# RPi_Extension_weight.net
KiCad netlist of a schematic drawn in EAGLE
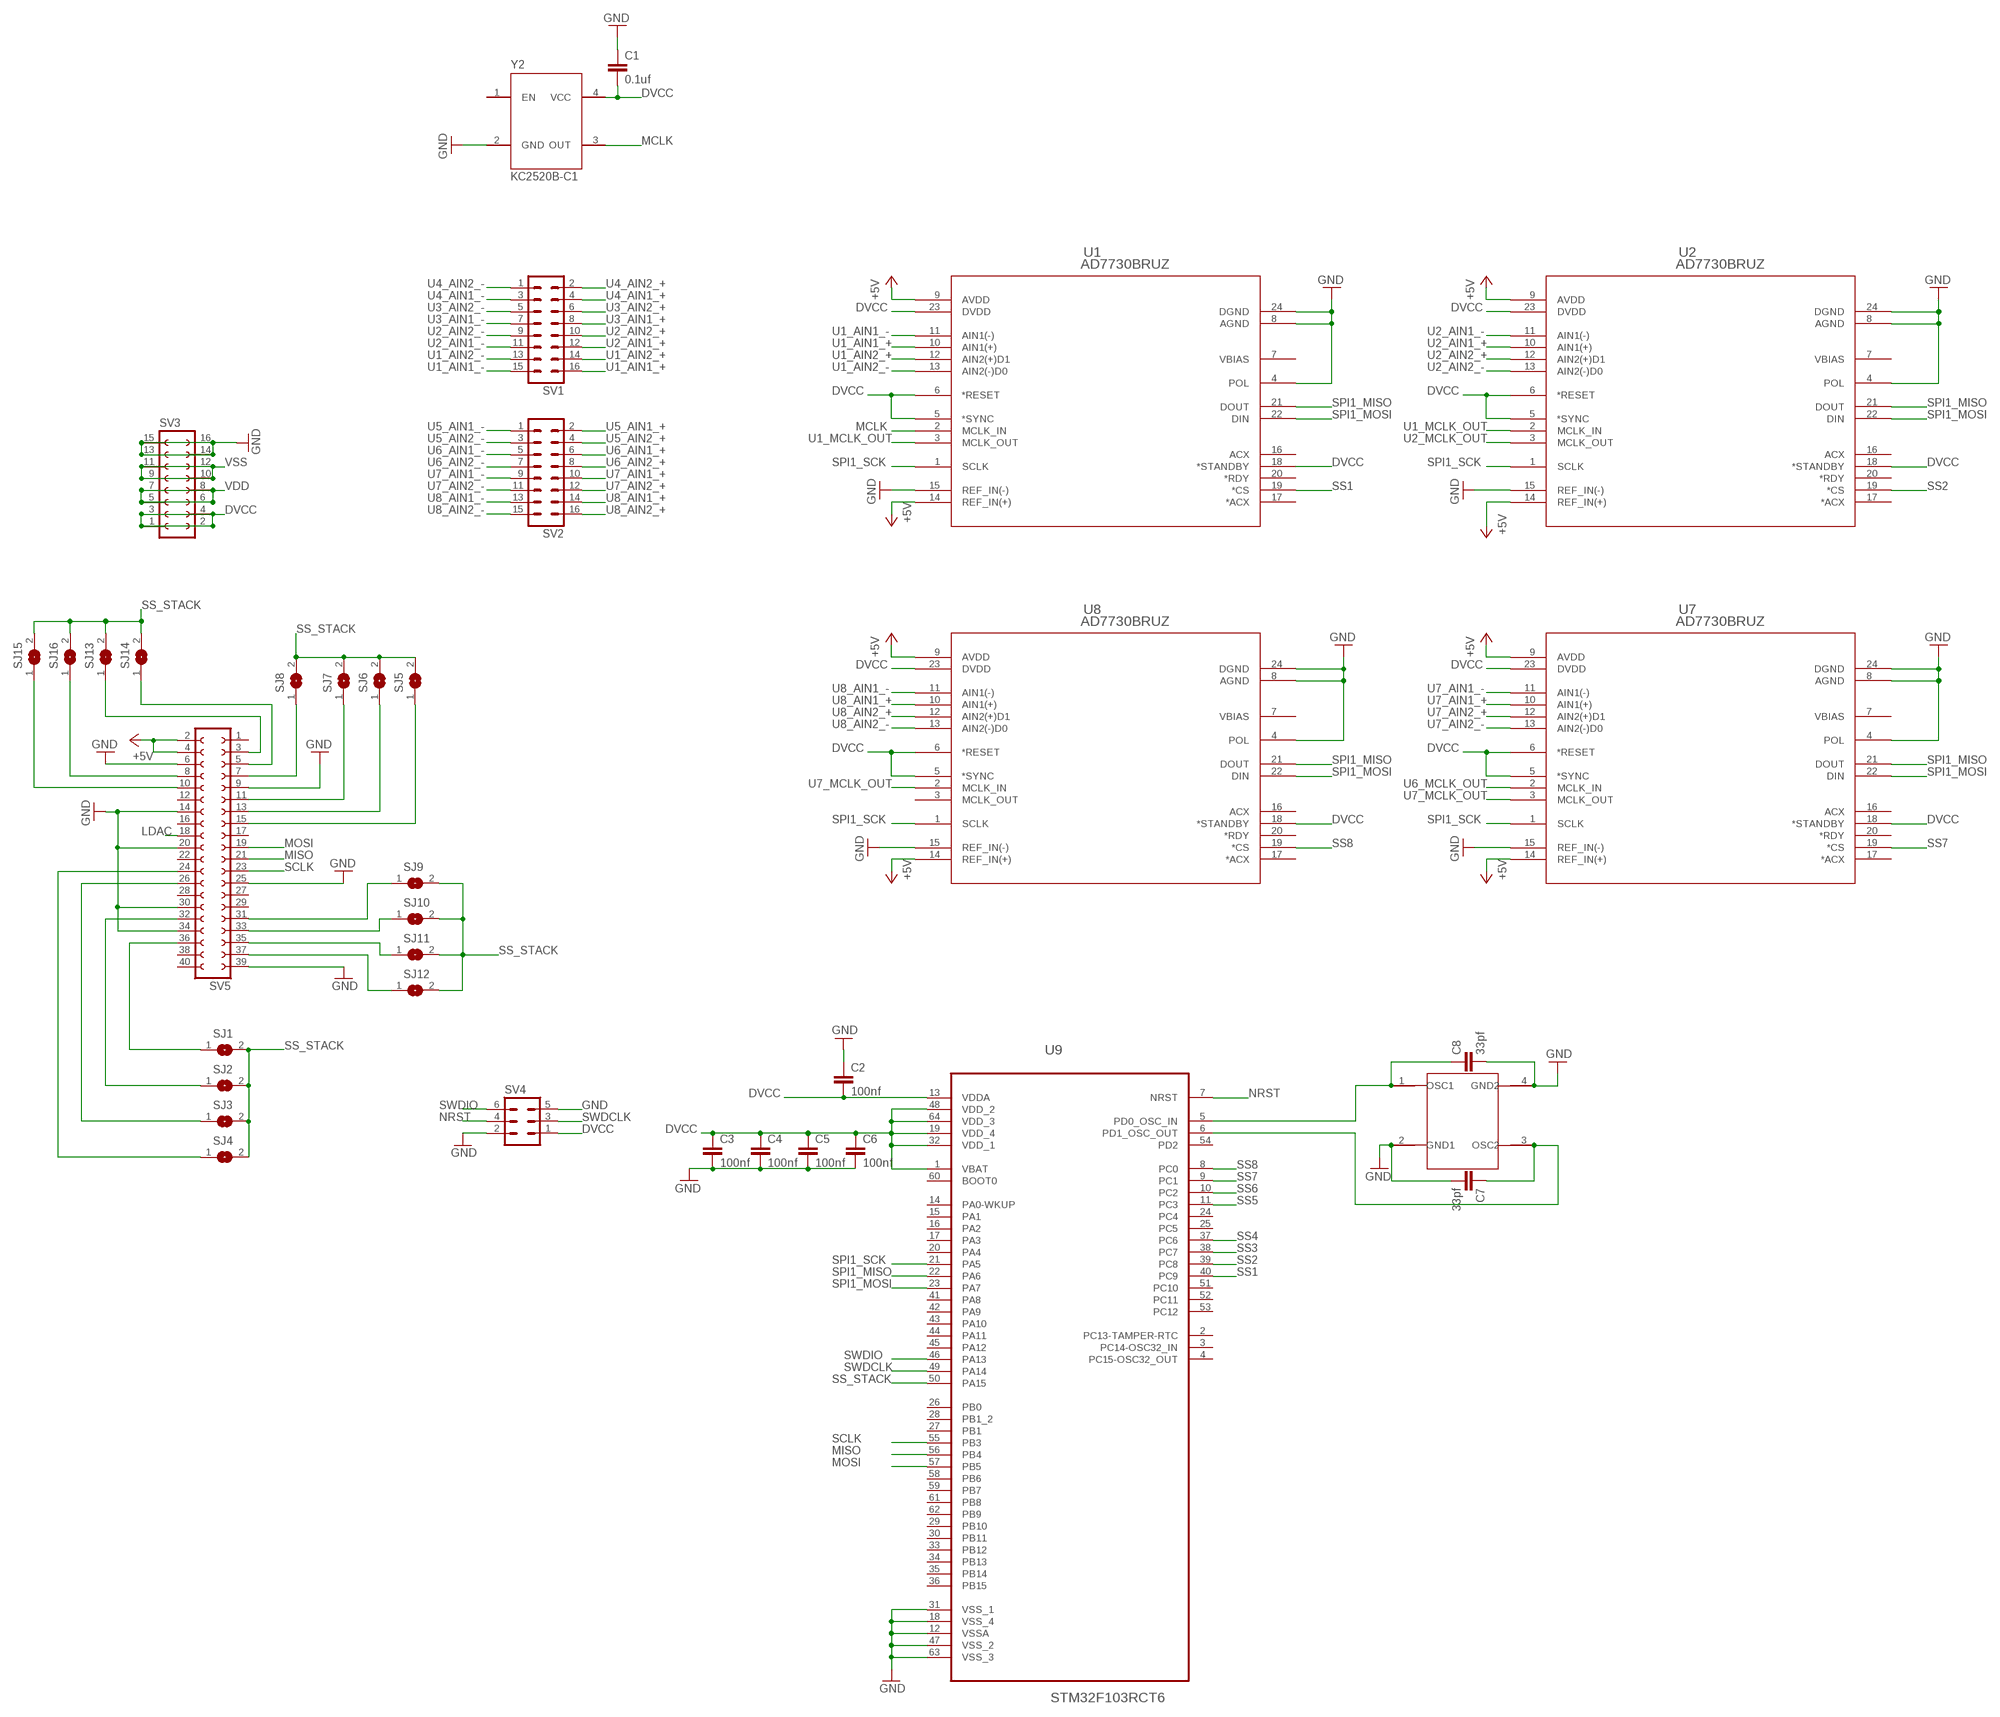
[diagram p0: schematic, sheet 1, part 1 of 2]
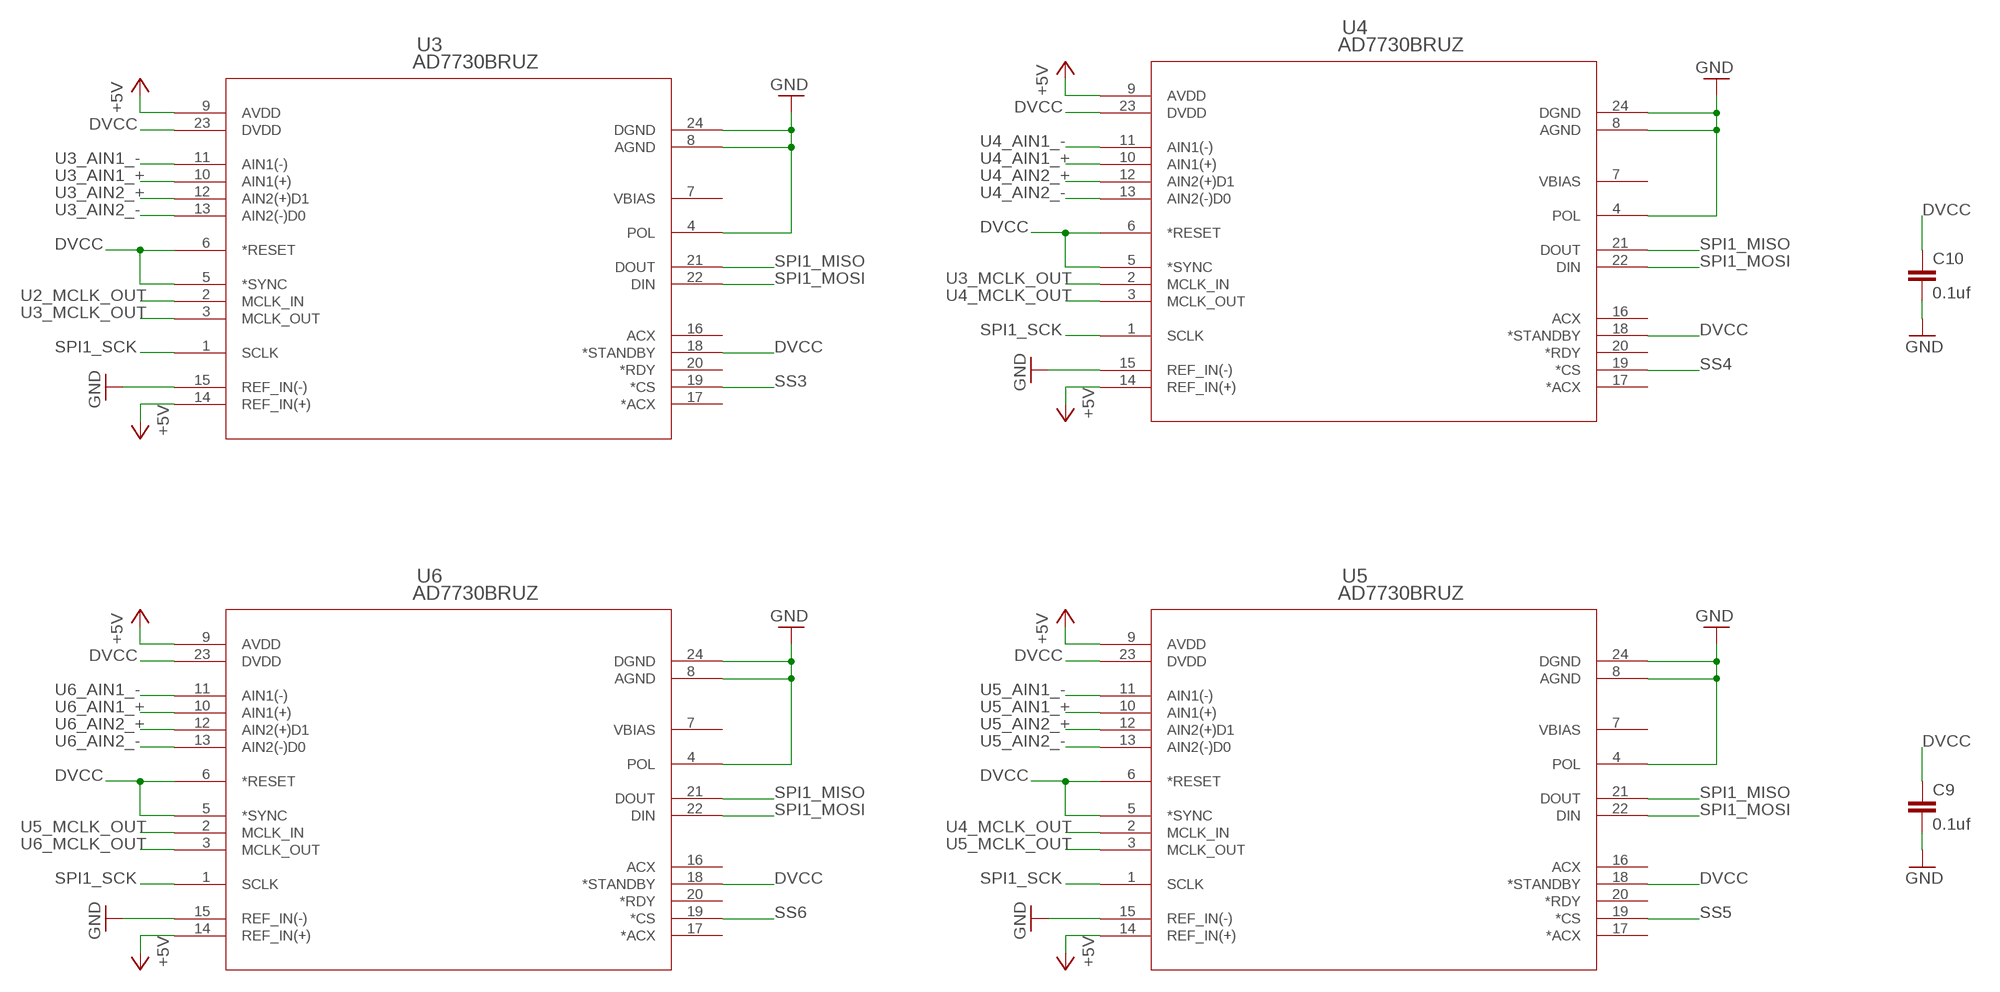
[diagram p1: schematic, sheet 1, part 2 of 2]

(export (version "E")
  (design (tool "Eeschema 10.0.6"))
  (components
    (comp (ref "C1")
      (value "0.1uf")
      (footprint "eagle-import:C0603")
      (libsource (lib "eagle-import") (part "C-EUC0603"))
    )
    (comp (ref "C2")
      (value "100nf")
      (footprint "eagle-import:C0603")
      (libsource (lib "eagle-import") (part "C-EUC0603"))
    )
    (comp (ref "C3")
      (value "100nf")
      (footprint "eagle-import:C0603")
      (libsource (lib "eagle-import") (part "C-EUC0603"))
    )
    (comp (ref "C4")
      (value "100nf")
      (footprint "eagle-import:C0603")
      (libsource (lib "eagle-import") (part "C-EUC0603"))
    )
    (comp (ref "C5")
      (value "100nf")
      (footprint "eagle-import:C0603")
      (libsource (lib "eagle-import") (part "C-EUC0603"))
    )
    (comp (ref "C6")
      (value "100nf")
      (footprint "eagle-import:C0603")
      (libsource (lib "eagle-import") (part "C-EUC0603"))
    )
    (comp (ref "C7")
      (value "33pf")
      (footprint "eagle-import:C0603")
      (libsource (lib "eagle-import") (part "C-EUC0603"))
    )
    (comp (ref "C8")
      (value "33pf")
      (footprint "eagle-import:C0603")
      (libsource (lib "eagle-import") (part "C-EUC0603"))
    )
    (comp (ref "C9")
      (value "0.1uf")
      (footprint "eagle-import:C0603")
      (libsource (lib "eagle-import") (part "C-EUC0603"))
    )
    (comp (ref "C10")
      (value "0.1uf")
      (footprint "eagle-import:C0603")
      (libsource (lib "eagle-import") (part "C-EUC0603"))
    )
    (comp (ref "SJ1") (value "SJ") (footprint "eagle-import:SJ") (libsource (lib "eagle-import") (part "SJ")))
    (comp (ref "SJ2") (value "SJ") (footprint "eagle-import:SJ") (libsource (lib "eagle-import") (part "SJ")))
    (comp (ref "SJ3") (value "SJ") (footprint "eagle-import:SJ") (libsource (lib "eagle-import") (part "SJ")))
    (comp (ref "SJ4") (value "SJ") (footprint "eagle-import:SJ") (libsource (lib "eagle-import") (part "SJ")))
    (comp (ref "SJ5") (value "SJ") (footprint "eagle-import:SJ") (libsource (lib "eagle-import") (part "SJ")))
    (comp (ref "SJ6") (value "SJ") (footprint "eagle-import:SJ") (libsource (lib "eagle-import") (part "SJ")))
    (comp (ref "SJ7") (value "SJ") (footprint "eagle-import:SJ") (libsource (lib "eagle-import") (part "SJ")))
    (comp (ref "SJ8") (value "SJ") (footprint "eagle-import:SJ") (libsource (lib "eagle-import") (part "SJ")))
    (comp (ref "SJ9") (value "SJ") (footprint "eagle-import:SJ") (libsource (lib "eagle-import") (part "SJ")))
    (comp (ref "SJ10")
      (value "SJ")
      (footprint "eagle-import:SJ")
      (libsource (lib "eagle-import") (part "SJ"))
    )
    (comp (ref "SJ11")
      (value "SJ")
      (footprint "eagle-import:SJ")
      (libsource (lib "eagle-import") (part "SJ"))
    )
    (comp (ref "SJ12")
      (value "SJ")
      (footprint "eagle-import:SJ")
      (libsource (lib "eagle-import") (part "SJ"))
    )
    (comp (ref "SJ13")
      (value "SJ")
      (footprint "eagle-import:SJ")
      (libsource (lib "eagle-import") (part "SJ"))
    )
    (comp (ref "SJ14")
      (value "SJ")
      (footprint "eagle-import:SJ")
      (libsource (lib "eagle-import") (part "SJ"))
    )
    (comp (ref "SJ15")
      (value "SJ")
      (footprint "eagle-import:SJ")
      (libsource (lib "eagle-import") (part "SJ"))
    )
    (comp (ref "SJ16")
      (value "SJ")
      (footprint "eagle-import:SJ")
      (libsource (lib "eagle-import") (part "SJ"))
    )
    (comp (ref "SV1")
      (value "MA08-2W")
      (footprint "eagle-import:MA08-2W")
      (libsource (lib "eagle-import") (part "MA08-2W"))
    )
    (comp (ref "SV2")
      (value "MA08-2W")
      (footprint "eagle-import:MA08-2W")
      (libsource (lib "eagle-import") (part "MA08-2W"))
    )
    (comp (ref "SV3")
      (value "FE08-2")
      (footprint "eagle-import:FE08-2")
      (libsource (lib "eagle-import") (part "FE08-2"))
    )
    (comp (ref "SV4")
      (value "MA03-2")
      (footprint "eagle-import:MA03-2")
      (libsource (lib "eagle-import") (part "MA03-2"))
    )
    (comp (ref "SV5")
      (value "FE20-2")
      (footprint "eagle-import:FE20-2")
      (libsource (lib "eagle-import") (part "FE20-2"))
    )
    (comp (ref "U1")
      (value "AD7730BRUZ")
      (footprint "eagle-import:RU_24")
      (libsource (lib "eagle-import") (part "AD7730BRUZ"))
    )
    (comp (ref "U2")
      (value "AD7730BRUZ")
      (footprint "eagle-import:RU_24")
      (libsource (lib "eagle-import") (part "AD7730BRUZ"))
    )
    (comp (ref "U3")
      (value "AD7730BRUZ")
      (footprint "eagle-import:RU_24")
      (libsource (lib "eagle-import") (part "AD7730BRUZ"))
    )
    (comp (ref "U4")
      (value "AD7730BRUZ")
      (footprint "eagle-import:RU_24")
      (libsource (lib "eagle-import") (part "AD7730BRUZ"))
    )
    (comp (ref "U5")
      (value "AD7730BRUZ")
      (footprint "eagle-import:RU_24")
      (libsource (lib "eagle-import") (part "AD7730BRUZ"))
    )
    (comp (ref "U6")
      (value "AD7730BRUZ")
      (footprint "eagle-import:RU_24")
      (libsource (lib "eagle-import") (part "AD7730BRUZ"))
    )
    (comp (ref "U7")
      (value "AD7730BRUZ")
      (footprint "eagle-import:RU_24")
      (libsource (lib "eagle-import") (part "AD7730BRUZ"))
    )
    (comp (ref "U8")
      (value "AD7730BRUZ")
      (footprint "eagle-import:RU_24")
      (libsource (lib "eagle-import") (part "AD7730BRUZ"))
    )
    (comp (ref "U9")
      (value "STM32F103RCT6")
      (footprint "eagle-import:QFP50P1200X1200X160-64N")
      (libsource (lib "eagle-import") (part "STM32F103RCT6"))
    )
    (comp (ref "Y1")
      (value "ABM3B")
      (footprint "eagle-import:ABM3B")
      (libsource (lib "eagle-import") (part "ABM3B"))
    )
    (comp (ref "Y2")
      (value "KC2520B-C1")
      (footprint "eagle-import:KC2520B-C1")
      (libsource (lib "eagle-import") (part "KC2520B-C1"))
    )
  )
  (nets
    (net (code "1") (name "+5V") (class "Default")
      (node (ref "SV5") (pin "2") (pinfunction "2_2") (pintype "passive"))
      (node (ref "SV5") (pin "4") (pinfunction "4_4") (pintype "passive"))
      (node (ref "U1") (pin "14") (pinfunction "REF_IN(+)_14") (pintype "passive"))
      (node (ref "U1") (pin "9") (pinfunction "AVDD_9") (pintype "passive"))
      (node (ref "U2") (pin "14") (pinfunction "REF_IN(+)_14") (pintype "passive"))
      (node (ref "U2") (pin "9") (pinfunction "AVDD_9") (pintype "passive"))
      (node (ref "U3") (pin "14") (pinfunction "REF_IN(+)_14") (pintype "passive"))
      (node (ref "U3") (pin "9") (pinfunction "AVDD_9") (pintype "passive"))
      (node (ref "U4") (pin "14") (pinfunction "REF_IN(+)_14") (pintype "passive"))
      (node (ref "U4") (pin "9") (pinfunction "AVDD_9") (pintype "passive"))
      (node (ref "U5") (pin "14") (pinfunction "REF_IN(+)_14") (pintype "passive"))
      (node (ref "U5") (pin "9") (pinfunction "AVDD_9") (pintype "passive"))
      (node (ref "U6") (pin "14") (pinfunction "REF_IN(+)_14") (pintype "passive"))
      (node (ref "U6") (pin "9") (pinfunction "AVDD_9") (pintype "passive"))
      (node (ref "U7") (pin "14") (pinfunction "REF_IN(+)_14") (pintype "passive"))
      (node (ref "U7") (pin "9") (pinfunction "AVDD_9") (pintype "passive"))
      (node (ref "U8") (pin "14") (pinfunction "REF_IN(+)_14") (pintype "passive"))
      (node (ref "U8") (pin "9") (pinfunction "AVDD_9") (pintype "passive"))
    )
    (net (code "2") (name "/DVCC") (class "Default")
      (node (ref "C1") (pin "2") (pinfunction "2_2") (pintype "passive"))
      (node (ref "C10") (pin "1") (pinfunction "1_1") (pintype "passive"))
      (node (ref "C2") (pin "2") (pinfunction "2_2") (pintype "passive"))
      (node (ref "C3") (pin "1") (pinfunction "1_1") (pintype "passive"))
      (node (ref "C4") (pin "1") (pinfunction "1_1") (pintype "passive"))
      (node (ref "C5") (pin "1") (pinfunction "1_1") (pintype "passive"))
      (node (ref "C6") (pin "1") (pinfunction "1_1") (pintype "passive"))
      (node (ref "C9") (pin "1") (pinfunction "1_1") (pintype "passive"))
      (node (ref "SV3") (pin "1") (pinfunction "1_1") (pintype "passive"))
      (node (ref "SV3") (pin "2") (pinfunction "2_2") (pintype "passive"))
      (node (ref "SV3") (pin "3") (pinfunction "3_3") (pintype "passive"))
      (node (ref "SV3") (pin "4") (pinfunction "4_4") (pintype "passive"))
      (node (ref "SV4") (pin "1") (pinfunction "1_1") (pintype "passive"))
      (node (ref "U1") (pin "18") (pinfunction "*STANDBY_18") (pintype "passive"))
      (node (ref "U1") (pin "23") (pinfunction "DVDD_23") (pintype "passive"))
      (node (ref "U1") (pin "5") (pinfunction "*SYNC_5") (pintype "passive"))
      (node (ref "U1") (pin "6") (pinfunction "*RESET_6") (pintype "passive"))
      (node (ref "U2") (pin "18") (pinfunction "*STANDBY_18") (pintype "passive"))
      (node (ref "U2") (pin "23") (pinfunction "DVDD_23") (pintype "passive"))
      (node (ref "U2") (pin "5") (pinfunction "*SYNC_5") (pintype "passive"))
      (node (ref "U2") (pin "6") (pinfunction "*RESET_6") (pintype "passive"))
      (node (ref "U3") (pin "18") (pinfunction "*STANDBY_18") (pintype "passive"))
      (node (ref "U3") (pin "23") (pinfunction "DVDD_23") (pintype "passive"))
      (node (ref "U3") (pin "5") (pinfunction "*SYNC_5") (pintype "passive"))
      (node (ref "U3") (pin "6") (pinfunction "*RESET_6") (pintype "passive"))
      (node (ref "U4") (pin "18") (pinfunction "*STANDBY_18") (pintype "passive"))
      (node (ref "U4") (pin "23") (pinfunction "DVDD_23") (pintype "passive"))
      (node (ref "U4") (pin "5") (pinfunction "*SYNC_5") (pintype "passive"))
      (node (ref "U4") (pin "6") (pinfunction "*RESET_6") (pintype "passive"))
      (node (ref "U5") (pin "18") (pinfunction "*STANDBY_18") (pintype "passive"))
      (node (ref "U5") (pin "23") (pinfunction "DVDD_23") (pintype "passive"))
      (node (ref "U5") (pin "5") (pinfunction "*SYNC_5") (pintype "passive"))
      (node (ref "U5") (pin "6") (pinfunction "*RESET_6") (pintype "passive"))
      (node (ref "U6") (pin "18") (pinfunction "*STANDBY_18") (pintype "passive"))
      (node (ref "U6") (pin "23") (pinfunction "DVDD_23") (pintype "passive"))
      (node (ref "U6") (pin "5") (pinfunction "*SYNC_5") (pintype "passive"))
      (node (ref "U6") (pin "6") (pinfunction "*RESET_6") (pintype "passive"))
      (node (ref "U7") (pin "18") (pinfunction "*STANDBY_18") (pintype "passive"))
      (node (ref "U7") (pin "23") (pinfunction "DVDD_23") (pintype "passive"))
      (node (ref "U7") (pin "5") (pinfunction "*SYNC_5") (pintype "passive"))
      (node (ref "U7") (pin "6") (pinfunction "*RESET_6") (pintype "passive"))
      (node (ref "U8") (pin "18") (pinfunction "*STANDBY_18") (pintype "passive"))
      (node (ref "U8") (pin "23") (pinfunction "DVDD_23") (pintype "passive"))
      (node (ref "U8") (pin "5") (pinfunction "*SYNC_5") (pintype "passive"))
      (node (ref "U8") (pin "6") (pinfunction "*RESET_6") (pintype "passive"))
      (node (ref "U9") (pin "1") (pinfunction "VBAT_1") (pintype "input"))
      (node (ref "U9") (pin "13") (pinfunction "VDDA_13") (pintype "power_in"))
      (node (ref "U9") (pin "19") (pinfunction "VDD_4_19") (pintype "power_in"))
      (node (ref "U9") (pin "32") (pinfunction "VDD_1_32") (pintype "power_in"))
      (node (ref "U9") (pin "48") (pinfunction "VDD_2_48") (pintype "power_in"))
      (node (ref "U9") (pin "64") (pinfunction "VDD_3_64") (pintype "power_in"))
      (node (ref "Y2") (pin "4") (pinfunction "VCC_4") (pintype "bidirectional"))
    )
    (net (code "3") (name "/LDAC") (class "Default")
      (node (ref "SV5") (pin "18") (pinfunction "18_18") (pintype "passive"))
    )
    (net (code "4") (name "/MCLK") (class "Default")
      (node (ref "U1") (pin "2") (pinfunction "MCLK_IN_2") (pintype "passive"))
      (node (ref "Y2") (pin "3") (pinfunction "OUT_3") (pintype "bidirectional"))
    )
    (net (code "5") (name "/MISO") (class "Default")
      (node (ref "SV5") (pin "21") (pinfunction "21_21") (pintype "passive"))
      (node (ref "U9") (pin "56") (pinfunction "PB4_56") (pintype "bidirectional"))
    )
    (net (code "6") (name "/MOSI") (class "Default")
      (node (ref "SV5") (pin "19") (pinfunction "19_19") (pintype "passive"))
      (node (ref "U9") (pin "57") (pinfunction "PB5_57") (pintype "bidirectional"))
    )
    (net (code "7") (name "/NRST") (class "Default")
      (node (ref "SV4") (pin "4") (pinfunction "4_4") (pintype "passive"))
      (node (ref "U9") (pin "7") (pinfunction "NRST_7") (pintype "output"))
    )
    (net (code "8") (name "/PB7") (class "Default")
      (node (ref "U9") (pin "59") (pinfunction "PB7_59") (pintype "power_in"))
    )
    (net (code "9") (name "/SCLK") (class "Default")
      (node (ref "SV5") (pin "23") (pinfunction "23_23") (pintype "passive"))
      (node (ref "U9") (pin "55") (pinfunction "PB3_55") (pintype "bidirectional"))
    )
    (net (code "10") (name "/SPI1_MISO") (class "Default")
      (node (ref "U1") (pin "21") (pinfunction "DOUT_21") (pintype "passive"))
      (node (ref "U2") (pin "21") (pinfunction "DOUT_21") (pintype "passive"))
      (node (ref "U3") (pin "21") (pinfunction "DOUT_21") (pintype "passive"))
      (node (ref "U4") (pin "21") (pinfunction "DOUT_21") (pintype "passive"))
      (node (ref "U5") (pin "21") (pinfunction "DOUT_21") (pintype "passive"))
      (node (ref "U6") (pin "21") (pinfunction "DOUT_21") (pintype "passive"))
      (node (ref "U7") (pin "21") (pinfunction "DOUT_21") (pintype "passive"))
      (node (ref "U8") (pin "21") (pinfunction "DOUT_21") (pintype "passive"))
      (node (ref "U9") (pin "22") (pinfunction "PA6_22") (pintype "bidirectional"))
    )
    (net (code "11") (name "/SPI1_MOSI") (class "Default")
      (node (ref "U1") (pin "22") (pinfunction "DIN_22") (pintype "passive"))
      (node (ref "U2") (pin "22") (pinfunction "DIN_22") (pintype "passive"))
      (node (ref "U3") (pin "22") (pinfunction "DIN_22") (pintype "passive"))
      (node (ref "U4") (pin "22") (pinfunction "DIN_22") (pintype "passive"))
      (node (ref "U5") (pin "22") (pinfunction "DIN_22") (pintype "passive"))
      (node (ref "U6") (pin "22") (pinfunction "DIN_22") (pintype "passive"))
      (node (ref "U7") (pin "22") (pinfunction "DIN_22") (pintype "passive"))
      (node (ref "U8") (pin "22") (pinfunction "DIN_22") (pintype "passive"))
      (node (ref "U9") (pin "23") (pinfunction "PA7_23") (pintype "power_in"))
    )
    (net (code "12") (name "/SPI1_SCK") (class "Default")
      (node (ref "U1") (pin "1") (pinfunction "SCLK_1") (pintype "passive"))
      (node (ref "U2") (pin "1") (pinfunction "SCLK_1") (pintype "passive"))
      (node (ref "U3") (pin "1") (pinfunction "SCLK_1") (pintype "passive"))
      (node (ref "U4") (pin "1") (pinfunction "SCLK_1") (pintype "passive"))
      (node (ref "U5") (pin "1") (pinfunction "SCLK_1") (pintype "passive"))
      (node (ref "U6") (pin "1") (pinfunction "SCLK_1") (pintype "passive"))
      (node (ref "U7") (pin "1") (pinfunction "SCLK_1") (pintype "passive"))
      (node (ref "U8") (pin "1") (pinfunction "SCLK_1") (pintype "passive"))
      (node (ref "U9") (pin "21") (pinfunction "PA5_21") (pintype "bidirectional"))
    )
    (net (code "13") (name "/SS1") (class "Default")
      (node (ref "U1") (pin "19") (pinfunction "*CS_19") (pintype "passive"))
      (node (ref "U9") (pin "40") (pinfunction "PC9_40") (pintype "bidirectional"))
    )
    (net (code "14") (name "/SS2") (class "Default")
      (node (ref "U2") (pin "19") (pinfunction "*CS_19") (pintype "passive"))
      (node (ref "U9") (pin "39") (pinfunction "PC8_39") (pintype "bidirectional"))
    )
    (net (code "15") (name "/SS3") (class "Default")
      (node (ref "U3") (pin "19") (pinfunction "*CS_19") (pintype "passive"))
      (node (ref "U9") (pin "38") (pinfunction "PC7_38") (pintype "bidirectional"))
    )
    (net (code "16") (name "/SS4") (class "Default")
      (node (ref "U4") (pin "19") (pinfunction "*CS_19") (pintype "passive"))
      (node (ref "U9") (pin "37") (pinfunction "PC6_37") (pintype "bidirectional"))
    )
    (net (code "17") (name "/SS5") (class "Default")
      (node (ref "U5") (pin "19") (pinfunction "*CS_19") (pintype "passive"))
      (node (ref "U9") (pin "11") (pinfunction "PC3_11") (pintype "bidirectional"))
    )
    (net (code "18") (name "/SS6") (class "Default")
      (node (ref "U6") (pin "19") (pinfunction "*CS_19") (pintype "passive"))
      (node (ref "U9") (pin "10") (pinfunction "PC2_10") (pintype "bidirectional"))
    )
    (net (code "19") (name "/SS7") (class "Default")
      (node (ref "U7") (pin "19") (pinfunction "*CS_19") (pintype "passive"))
      (node (ref "U9") (pin "9") (pinfunction "PC1_9") (pintype "bidirectional"))
    )
    (net (code "20") (name "/SS8") (class "Default")
      (node (ref "U8") (pin "19") (pinfunction "*CS_19") (pintype "passive"))
      (node (ref "U9") (pin "8") (pinfunction "PC0_8") (pintype "bidirectional"))
    )
    (net (code "21") (name "/SS_STACK") (class "Default")
      (node (ref "SJ1") (pin "2") (pinfunction "2_2") (pintype "passive"))
      (node (ref "SJ10") (pin "2") (pinfunction "2_2") (pintype "passive"))
      (node (ref "SJ11") (pin "2") (pinfunction "2_2") (pintype "passive"))
      (node (ref "SJ12") (pin "2") (pinfunction "2_2") (pintype "passive"))
      (node (ref "SJ13") (pin "2") (pinfunction "2_2") (pintype "passive"))
      (node (ref "SJ14") (pin "2") (pinfunction "2_2") (pintype "passive"))
      (node (ref "SJ15") (pin "2") (pinfunction "2_2") (pintype "passive"))
      (node (ref "SJ16") (pin "2") (pinfunction "2_2") (pintype "passive"))
      (node (ref "SJ2") (pin "2") (pinfunction "2_2") (pintype "passive"))
      (node (ref "SJ3") (pin "2") (pinfunction "2_2") (pintype "passive"))
      (node (ref "SJ4") (pin "2") (pinfunction "2_2") (pintype "passive"))
      (node (ref "SJ5") (pin "2") (pinfunction "2_2") (pintype "passive"))
      (node (ref "SJ6") (pin "2") (pinfunction "2_2") (pintype "passive"))
      (node (ref "SJ7") (pin "2") (pinfunction "2_2") (pintype "passive"))
      (node (ref "SJ8") (pin "2") (pinfunction "2_2") (pintype "passive"))
      (node (ref "SJ9") (pin "2") (pinfunction "2_2") (pintype "passive"))
      (node (ref "U9") (pin "50") (pinfunction "PA15_50") (pintype "bidirectional"))
    )
    (net (code "22") (name "/SWDCLK") (class "Default")
      (node (ref "SV4") (pin "3") (pinfunction "3_3") (pintype "passive"))
      (node (ref "U9") (pin "49") (pinfunction "PA14_49") (pintype "bidirectional"))
    )
    (net (code "23") (name "/SWDIO") (class "Default")
      (node (ref "SV4") (pin "6") (pinfunction "6_6") (pintype "passive"))
      (node (ref "U9") (pin "46") (pinfunction "PA13_46") (pintype "bidirectional"))
    )
    (net (code "24") (name "/U1_AIN1_+") (class "Default")
      (node (ref "SV1") (pin "16") (pinfunction "16_16") (pintype "passive"))
      (node (ref "U1") (pin "10") (pinfunction "AIN1(+)_10") (pintype "passive"))
    )
    (net (code "25") (name "/U1_AIN1_-") (class "Default")
      (node (ref "SV1") (pin "15") (pinfunction "15_15") (pintype "passive"))
      (node (ref "U1") (pin "11") (pinfunction "AIN1(-)_11") (pintype "passive"))
    )
    (net (code "26") (name "/U1_AIN2_+") (class "Default")
      (node (ref "SV1") (pin "14") (pinfunction "14_14") (pintype "passive"))
      (node (ref "U1") (pin "12") (pinfunction "AIN2(+)D1_12") (pintype "passive"))
    )
    (net (code "27") (name "/U1_AIN2_-") (class "Default")
      (node (ref "SV1") (pin "13") (pinfunction "13_13") (pintype "passive"))
      (node (ref "U1") (pin "13") (pinfunction "AIN2(-)D0_13") (pintype "passive"))
    )
    (net (code "28") (name "/U1_MCLK_OUT") (class "Default")
      (node (ref "U1") (pin "3") (pinfunction "MCLK_OUT_3") (pintype "passive"))
      (node (ref "U2") (pin "2") (pinfunction "MCLK_IN_2") (pintype "passive"))
    )
    (net (code "29") (name "/U2_AIN1_+") (class "Default")
      (node (ref "SV1") (pin "12") (pinfunction "12_12") (pintype "passive"))
      (node (ref "U2") (pin "10") (pinfunction "AIN1(+)_10") (pintype "passive"))
    )
    (net (code "30") (name "/U2_AIN1_-") (class "Default")
      (node (ref "SV1") (pin "11") (pinfunction "11_11") (pintype "passive"))
      (node (ref "U2") (pin "11") (pinfunction "AIN1(-)_11") (pintype "passive"))
    )
    (net (code "31") (name "/U2_AIN2_+") (class "Default")
      (node (ref "SV1") (pin "10") (pinfunction "10_10") (pintype "passive"))
      (node (ref "U2") (pin "12") (pinfunction "AIN2(+)D1_12") (pintype "passive"))
    )
    (net (code "32") (name "/U2_AIN2_-") (class "Default")
      (node (ref "SV1") (pin "9") (pinfunction "9_9") (pintype "passive"))
      (node (ref "U2") (pin "13") (pinfunction "AIN2(-)D0_13") (pintype "passive"))
    )
    (net (code "33") (name "/U2_MCLK_OUT") (class "Default")
      (node (ref "U2") (pin "3") (pinfunction "MCLK_OUT_3") (pintype "passive"))
      (node (ref "U3") (pin "2") (pinfunction "MCLK_IN_2") (pintype "passive"))
    )
    (net (code "34") (name "/U3_AIN1_+") (class "Default")
      (node (ref "SV1") (pin "8") (pinfunction "8_8") (pintype "passive"))
      (node (ref "U3") (pin "10") (pinfunction "AIN1(+)_10") (pintype "passive"))
    )
    (net (code "35") (name "/U3_AIN1_-") (class "Default")
      (node (ref "SV1") (pin "7") (pinfunction "7_7") (pintype "passive"))
      (node (ref "U3") (pin "11") (pinfunction "AIN1(-)_11") (pintype "passive"))
    )
    (net (code "36") (name "/U3_AIN2_+") (class "Default")
      (node (ref "SV1") (pin "6") (pinfunction "6_6") (pintype "passive"))
      (node (ref "U3") (pin "12") (pinfunction "AIN2(+)D1_12") (pintype "passive"))
    )
    (net (code "37") (name "/U3_AIN2_-") (class "Default")
      (node (ref "SV1") (pin "5") (pinfunction "5_5") (pintype "passive"))
      (node (ref "U3") (pin "13") (pinfunction "AIN2(-)D0_13") (pintype "passive"))
    )
    (net (code "38") (name "/U3_MCLK_OUT") (class "Default")
      (node (ref "U3") (pin "3") (pinfunction "MCLK_OUT_3") (pintype "passive"))
      (node (ref "U4") (pin "2") (pinfunction "MCLK_IN_2") (pintype "passive"))
    )
    (net (code "39") (name "/U4_AIN1_+") (class "Default")
      (node (ref "SV1") (pin "4") (pinfunction "4_4") (pintype "passive"))
      (node (ref "U4") (pin "10") (pinfunction "AIN1(+)_10") (pintype "passive"))
    )
    (net (code "40") (name "/U4_AIN1_-") (class "Default")
      (node (ref "SV1") (pin "3") (pinfunction "3_3") (pintype "passive"))
      (node (ref "U4") (pin "11") (pinfunction "AIN1(-)_11") (pintype "passive"))
    )
    (net (code "41") (name "/U4_AIN2_+") (class "Default")
      (node (ref "SV1") (pin "2") (pinfunction "2_2") (pintype "passive"))
      (node (ref "U4") (pin "12") (pinfunction "AIN2(+)D1_12") (pintype "passive"))
    )
    (net (code "42") (name "/U4_AIN2_-") (class "Default")
      (node (ref "SV1") (pin "1") (pinfunction "1_1") (pintype "passive"))
      (node (ref "U4") (pin "13") (pinfunction "AIN2(-)D0_13") (pintype "passive"))
    )
    (net (code "43") (name "/U4_MCLK_OUT") (class "Default")
      (node (ref "U4") (pin "3") (pinfunction "MCLK_OUT_3") (pintype "passive"))
      (node (ref "U5") (pin "2") (pinfunction "MCLK_IN_2") (pintype "passive"))
    )
    (net (code "44") (name "/U5_AIN1_+") (class "Default")
      (node (ref "SV2") (pin "2") (pinfunction "2_2") (pintype "passive"))
      (node (ref "U5") (pin "10") (pinfunction "AIN1(+)_10") (pintype "passive"))
    )
    (net (code "45") (name "/U5_AIN1_-") (class "Default")
      (node (ref "SV2") (pin "1") (pinfunction "1_1") (pintype "passive"))
      (node (ref "U5") (pin "11") (pinfunction "AIN1(-)_11") (pintype "passive"))
    )
    (net (code "46") (name "/U5_AIN2_+") (class "Default")
      (node (ref "SV2") (pin "4") (pinfunction "4_4") (pintype "passive"))
      (node (ref "U5") (pin "12") (pinfunction "AIN2(+)D1_12") (pintype "passive"))
    )
    (net (code "47") (name "/U5_AIN2_-") (class "Default")
      (node (ref "SV2") (pin "3") (pinfunction "3_3") (pintype "passive"))
      (node (ref "U5") (pin "13") (pinfunction "AIN2(-)D0_13") (pintype "passive"))
    )
    (net (code "48") (name "/U5_MCLK_OUT") (class "Default")
      (node (ref "U5") (pin "3") (pinfunction "MCLK_OUT_3") (pintype "passive"))
      (node (ref "U6") (pin "2") (pinfunction "MCLK_IN_2") (pintype "passive"))
    )
    (net (code "49") (name "/U6_AIN1_+") (class "Default")
      (node (ref "SV2") (pin "6") (pinfunction "6_6") (pintype "passive"))
      (node (ref "U6") (pin "10") (pinfunction "AIN1(+)_10") (pintype "passive"))
    )
    (net (code "50") (name "/U6_AIN1_-") (class "Default")
      (node (ref "SV2") (pin "5") (pinfunction "5_5") (pintype "passive"))
      (node (ref "U6") (pin "11") (pinfunction "AIN1(-)_11") (pintype "passive"))
    )
    (net (code "51") (name "/U6_AIN2_+") (class "Default")
      (node (ref "SV2") (pin "8") (pinfunction "8_8") (pintype "passive"))
      (node (ref "U6") (pin "12") (pinfunction "AIN2(+)D1_12") (pintype "passive"))
    )
    (net (code "52") (name "/U6_AIN2_-") (class "Default")
      (node (ref "SV2") (pin "7") (pinfunction "7_7") (pintype "passive"))
      (node (ref "U6") (pin "13") (pinfunction "AIN2(-)D0_13") (pintype "passive"))
    )
    (net (code "53") (name "/U6_MCLK_OUT") (class "Default")
      (node (ref "U6") (pin "3") (pinfunction "MCLK_OUT_3") (pintype "passive"))
      (node (ref "U7") (pin "2") (pinfunction "MCLK_IN_2") (pintype "passive"))
    )
    (net (code "54") (name "/U7_AIN1_+") (class "Default")
      (node (ref "SV2") (pin "10") (pinfunction "10_10") (pintype "passive"))
      (node (ref "U7") (pin "10") (pinfunction "AIN1(+)_10") (pintype "passive"))
    )
    (net (code "55") (name "/U7_AIN1_-") (class "Default")
      (node (ref "SV2") (pin "9") (pinfunction "9_9") (pintype "passive"))
      (node (ref "U7") (pin "11") (pinfunction "AIN1(-)_11") (pintype "passive"))
    )
    (net (code "56") (name "/U7_AIN2_+") (class "Default")
      (node (ref "SV2") (pin "12") (pinfunction "12_12") (pintype "passive"))
      (node (ref "U7") (pin "12") (pinfunction "AIN2(+)D1_12") (pintype "passive"))
    )
    (net (code "57") (name "/U7_AIN2_-") (class "Default")
      (node (ref "SV2") (pin "11") (pinfunction "11_11") (pintype "passive"))
      (node (ref "U7") (pin "13") (pinfunction "AIN2(-)D0_13") (pintype "passive"))
    )
    (net (code "58") (name "/U7_MCLK_OUT") (class "Default")
      (node (ref "U7") (pin "3") (pinfunction "MCLK_OUT_3") (pintype "passive"))
      (node (ref "U8") (pin "2") (pinfunction "MCLK_IN_2") (pintype "passive"))
    )
    (net (code "59") (name "/U8_AIN1_+") (class "Default")
      (node (ref "SV2") (pin "14") (pinfunction "14_14") (pintype "passive"))
      (node (ref "U8") (pin "10") (pinfunction "AIN1(+)_10") (pintype "passive"))
    )
    (net (code "60") (name "/U8_AIN1_-") (class "Default")
      (node (ref "SV2") (pin "13") (pinfunction "13_13") (pintype "passive"))
      (node (ref "U8") (pin "11") (pinfunction "AIN1(-)_11") (pintype "passive"))
    )
    (net (code "61") (name "/U8_AIN2_+") (class "Default")
      (node (ref "SV2") (pin "16") (pinfunction "16_16") (pintype "passive"))
      (node (ref "U8") (pin "12") (pinfunction "AIN2(+)D1_12") (pintype "passive"))
    )
    (net (code "62") (name "/U8_AIN2_-") (class "Default")
      (node (ref "SV2") (pin "15") (pinfunction "15_15") (pintype "passive"))
      (node (ref "U8") (pin "13") (pinfunction "AIN2(-)D0_13") (pintype "passive"))
    )
    (net (code "63") (name "/VDD") (class "Default")
      (node (ref "SV3") (pin "5") (pinfunction "5_5") (pintype "passive"))
      (node (ref "SV3") (pin "6") (pinfunction "6_6") (pintype "passive"))
      (node (ref "SV3") (pin "7") (pinfunction "7_7") (pintype "passive"))
      (node (ref "SV3") (pin "8") (pinfunction "8_8") (pintype "passive"))
    )
    (net (code "64") (name "/VSS") (class "Default")
      (node (ref "SV3") (pin "10") (pinfunction "10_10") (pintype "passive"))
      (node (ref "SV3") (pin "11") (pinfunction "11_11") (pintype "passive"))
      (node (ref "SV3") (pin "12") (pinfunction "12_12") (pintype "passive"))
      (node (ref "SV3") (pin "9") (pinfunction "9_9") (pintype "passive"))
    )
    (net (code "65") (name "GND") (class "Default")
      (node (ref "C1") (pin "1") (pinfunction "1_1") (pintype "passive"))
      (node (ref "C10") (pin "2") (pinfunction "2_2") (pintype "passive"))
      (node (ref "C2") (pin "1") (pinfunction "1_1") (pintype "passive"))
      (node (ref "C3") (pin "2") (pinfunction "2_2") (pintype "passive"))
      (node (ref "C4") (pin "2") (pinfunction "2_2") (pintype "passive"))
      (node (ref "C5") (pin "2") (pinfunction "2_2") (pintype "passive"))
      (node (ref "C6") (pin "2") (pinfunction "2_2") (pintype "passive"))
      (node (ref "C7") (pin "2") (pinfunction "2_2") (pintype "passive"))
      (node (ref "C8") (pin "2") (pinfunction "2_2") (pintype "passive"))
      (node (ref "C9") (pin "2") (pinfunction "2_2") (pintype "passive"))
      (node (ref "SV3") (pin "13") (pinfunction "13_13") (pintype "passive"))
      (node (ref "SV3") (pin "14") (pinfunction "14_14") (pintype "passive"))
      (node (ref "SV3") (pin "15") (pinfunction "15_15") (pintype "passive"))
      (node (ref "SV3") (pin "16") (pinfunction "16_16") (pintype "passive"))
      (node (ref "SV4") (pin "2") (pinfunction "2_2") (pintype "passive"))
      (node (ref "SV4") (pin "5") (pinfunction "5_5") (pintype "passive"))
      (node (ref "SV5") (pin "14") (pinfunction "14_14") (pintype "passive"))
      (node (ref "SV5") (pin "20") (pinfunction "20_20") (pintype "passive"))
      (node (ref "SV5") (pin "25") (pinfunction "25_25") (pintype "passive"))
      (node (ref "SV5") (pin "30") (pinfunction "30_30") (pintype "passive"))
      (node (ref "SV5") (pin "34") (pinfunction "34_34") (pintype "passive"))
      (node (ref "SV5") (pin "39") (pinfunction "39_39") (pintype "passive"))
      (node (ref "SV5") (pin "6") (pinfunction "6_6") (pintype "passive"))
      (node (ref "SV5") (pin "9") (pinfunction "9_9") (pintype "passive"))
      (node (ref "U1") (pin "15") (pinfunction "REF_IN(-)_15") (pintype "passive"))
      (node (ref "U1") (pin "24") (pinfunction "DGND_24") (pintype "passive"))
      (node (ref "U1") (pin "4") (pinfunction "POL_4") (pintype "passive"))
      (node (ref "U1") (pin "8") (pinfunction "AGND_8") (pintype "passive"))
      (node (ref "U2") (pin "15") (pinfunction "REF_IN(-)_15") (pintype "passive"))
      (node (ref "U2") (pin "24") (pinfunction "DGND_24") (pintype "passive"))
      (node (ref "U2") (pin "4") (pinfunction "POL_4") (pintype "passive"))
      (node (ref "U2") (pin "8") (pinfunction "AGND_8") (pintype "passive"))
      (node (ref "U3") (pin "15") (pinfunction "REF_IN(-)_15") (pintype "passive"))
      (node (ref "U3") (pin "24") (pinfunction "DGND_24") (pintype "passive"))
      (node (ref "U3") (pin "4") (pinfunction "POL_4") (pintype "passive"))
      (node (ref "U3") (pin "8") (pinfunction "AGND_8") (pintype "passive"))
      (node (ref "U4") (pin "15") (pinfunction "REF_IN(-)_15") (pintype "passive"))
      (node (ref "U4") (pin "24") (pinfunction "DGND_24") (pintype "passive"))
      (node (ref "U4") (pin "4") (pinfunction "POL_4") (pintype "passive"))
      (node (ref "U4") (pin "8") (pinfunction "AGND_8") (pintype "passive"))
      (node (ref "U5") (pin "15") (pinfunction "REF_IN(-)_15") (pintype "passive"))
      (node (ref "U5") (pin "24") (pinfunction "DGND_24") (pintype "passive"))
      (node (ref "U5") (pin "4") (pinfunction "POL_4") (pintype "passive"))
      (node (ref "U5") (pin "8") (pinfunction "AGND_8") (pintype "passive"))
      (node (ref "U6") (pin "15") (pinfunction "REF_IN(-)_15") (pintype "passive"))
      (node (ref "U6") (pin "24") (pinfunction "DGND_24") (pintype "passive"))
      (node (ref "U6") (pin "4") (pinfunction "POL_4") (pintype "passive"))
      (node (ref "U6") (pin "8") (pinfunction "AGND_8") (pintype "passive"))
      (node (ref "U7") (pin "15") (pinfunction "REF_IN(-)_15") (pintype "passive"))
      (node (ref "U7") (pin "24") (pinfunction "DGND_24") (pintype "passive"))
      (node (ref "U7") (pin "4") (pinfunction "POL_4") (pintype "passive"))
      (node (ref "U7") (pin "8") (pinfunction "AGND_8") (pintype "passive"))
      (node (ref "U8") (pin "15") (pinfunction "REF_IN(-)_15") (pintype "passive"))
      (node (ref "U8") (pin "24") (pinfunction "DGND_24") (pintype "passive"))
      (node (ref "U8") (pin "4") (pinfunction "POL_4") (pintype "passive"))
      (node (ref "U8") (pin "8") (pinfunction "AGND_8") (pintype "passive"))
      (node (ref "U9") (pin "12") (pinfunction "VSSA_12") (pintype "passive"))
      (node (ref "U9") (pin "18") (pinfunction "VSS_4_18") (pintype "passive"))
      (node (ref "U9") (pin "31") (pinfunction "VSS_1_31") (pintype "passive"))
      (node (ref "U9") (pin "47") (pinfunction "VSS_2_47") (pintype "passive"))
      (node (ref "U9") (pin "63") (pinfunction "VSS_3_63") (pintype "passive"))
      (node (ref "Y1") (pin "2") (pinfunction "GND1_2") (pintype "bidirectional"))
      (node (ref "Y1") (pin "4") (pinfunction "GND2_4") (pintype "bidirectional"))
      (node (ref "Y2") (pin "2") (pinfunction "GND_2") (pintype "bidirectional"))
    )
    (net (code "66") (name "Net-(SJ1-Pad1)") (class "Default")
      (node (ref "SJ1") (pin "1") (pinfunction "1_1") (pintype "passive"))
      (node (ref "SV5") (pin "36") (pinfunction "36_36") (pintype "passive"))
    )
    (net (code "67") (name "Net-(SJ2-Pad1)") (class "Default")
      (node (ref "SJ2") (pin "1") (pinfunction "1_1") (pintype "passive"))
      (node (ref "SV5") (pin "32") (pinfunction "32_32") (pintype "passive"))
    )
    (net (code "68") (name "Net-(SJ3-Pad1)") (class "Default")
      (node (ref "SJ3") (pin "1") (pinfunction "1_1") (pintype "passive"))
      (node (ref "SV5") (pin "26") (pinfunction "26_26") (pintype "passive"))
    )
    (net (code "69") (name "Net-(SJ4-Pad1)") (class "Default")
      (node (ref "SJ4") (pin "1") (pinfunction "1_1") (pintype "passive"))
      (node (ref "SV5") (pin "24") (pinfunction "24_24") (pintype "passive"))
    )
    (net (code "70") (name "Net-(SJ5-Pad1)") (class "Default")
      (node (ref "SJ5") (pin "1") (pinfunction "1_1") (pintype "passive"))
      (node (ref "SV5") (pin "15") (pinfunction "15_15") (pintype "passive"))
    )
    (net (code "71") (name "Net-(SJ6-Pad1)") (class "Default")
      (node (ref "SJ6") (pin "1") (pinfunction "1_1") (pintype "passive"))
      (node (ref "SV5") (pin "13") (pinfunction "13_13") (pintype "passive"))
    )
    (net (code "72") (name "Net-(SJ7-Pad1)") (class "Default")
      (node (ref "SJ7") (pin "1") (pinfunction "1_1") (pintype "passive"))
      (node (ref "SV5") (pin "11") (pinfunction "11_11") (pintype "passive"))
    )
    (net (code "73") (name "Net-(SJ8-Pad1)") (class "Default")
      (node (ref "SJ8") (pin "1") (pinfunction "1_1") (pintype "passive"))
      (node (ref "SV5") (pin "7") (pinfunction "7_7") (pintype "passive"))
    )
    (net (code "74") (name "Net-(SJ9-Pad1)") (class "Default")
      (node (ref "SJ9") (pin "1") (pinfunction "1_1") (pintype "passive"))
      (node (ref "SV5") (pin "31") (pinfunction "31_31") (pintype "passive"))
    )
    (net (code "75") (name "Net-(SJ10-Pad1)") (class "Default")
      (node (ref "SJ10") (pin "1") (pinfunction "1_1") (pintype "passive"))
      (node (ref "SV5") (pin "33") (pinfunction "33_33") (pintype "passive"))
    )
    (net (code "76") (name "Net-(SJ11-Pad1)") (class "Default")
      (node (ref "SJ11") (pin "1") (pinfunction "1_1") (pintype "passive"))
      (node (ref "SV5") (pin "35") (pinfunction "35_35") (pintype "passive"))
    )
    (net (code "77") (name "Net-(SJ12-Pad1)") (class "Default")
      (node (ref "SJ12") (pin "1") (pinfunction "1_1") (pintype "passive"))
      (node (ref "SV5") (pin "37") (pinfunction "37_37") (pintype "passive"))
    )
    (net (code "78") (name "Net-(SJ13-Pad1)") (class "Default")
      (node (ref "SJ13") (pin "1") (pinfunction "1_1") (pintype "passive"))
      (node (ref "SV5") (pin "3") (pinfunction "3_3") (pintype "passive"))
    )
    (net (code "79") (name "Net-(SJ14-Pad1)") (class "Default")
      (node (ref "SJ14") (pin "1") (pinfunction "1_1") (pintype "passive"))
      (node (ref "SV5") (pin "5") (pinfunction "5_5") (pintype "passive"))
    )
    (net (code "80") (name "Net-(SJ15-Pad1)") (class "Default")
      (node (ref "SJ15") (pin "1") (pinfunction "1_1") (pintype "passive"))
      (node (ref "SV5") (pin "10") (pinfunction "10_10") (pintype "passive"))
    )
    (net (code "81") (name "Net-(SJ16-Pad1)") (class "Default")
      (node (ref "SJ16") (pin "1") (pinfunction "1_1") (pintype "passive"))
      (node (ref "SV5") (pin "8") (pinfunction "8_8") (pintype "passive"))
    )
    (net (code "82") (name "Net-(U9-PD0_OSC_IN)") (class "Default")
      (node (ref "C8") (pin "1") (pinfunction "1_1") (pintype "passive"))
      (node (ref "U9") (pin "5") (pinfunction "PD0_OSC_IN_5") (pintype "input"))
      (node (ref "Y1") (pin "1") (pinfunction "OSC1_1") (pintype "bidirectional"))
    )
    (net (code "83") (name "Net-(U9-PD1_OSC_OUT)") (class "Default")
      (node (ref "C7") (pin "1") (pinfunction "1_1") (pintype "passive"))
      (node (ref "U9") (pin "6") (pinfunction "PD1_OSC_OUT_6") (pintype "output"))
      (node (ref "Y1") (pin "3") (pinfunction "OSC2_3") (pintype "bidirectional"))
    )
    (net (code "84") (name "unconnected-(SV5-Pad1)") (class "Default")
      (node (ref "SV5") (pin "1") (pinfunction "1_1") (pintype "passive"))
    )
    (net (code "85") (name "unconnected-(SV5-Pad12)") (class "Default")
      (node (ref "SV5") (pin "12") (pinfunction "12_12") (pintype "passive"))
    )
    (net (code "86") (name "unconnected-(SV5-Pad16)") (class "Default")
      (node (ref "SV5") (pin "16") (pinfunction "16_16") (pintype "passive"))
    )
    (net (code "87") (name "unconnected-(SV5-Pad17)") (class "Default")
      (node (ref "SV5") (pin "17") (pinfunction "17_17") (pintype "passive"))
    )
    (net (code "88") (name "unconnected-(SV5-Pad22)") (class "Default")
      (node (ref "SV5") (pin "22") (pinfunction "22_22") (pintype "passive"))
    )
    (net (code "89") (name "unconnected-(SV5-Pad27)") (class "Default")
      (node (ref "SV5") (pin "27") (pinfunction "27_27") (pintype "passive"))
    )
    (net (code "90") (name "unconnected-(SV5-Pad28)") (class "Default")
      (node (ref "SV5") (pin "28") (pinfunction "28_28") (pintype "passive"))
    )
    (net (code "91") (name "unconnected-(SV5-Pad29)") (class "Default")
      (node (ref "SV5") (pin "29") (pinfunction "29_29") (pintype "passive"))
    )
    (net (code "92") (name "unconnected-(SV5-Pad38)") (class "Default")
      (node (ref "SV5") (pin "38") (pinfunction "38_38") (pintype "passive"))
    )
    (net (code "93") (name "unconnected-(SV5-Pad40)") (class "Default")
      (node (ref "SV5") (pin "40") (pinfunction "40_40") (pintype "passive"))
    )
    (net (code "94") (name "unconnected-(U1-*ACX-Pad17)") (class "Default")
      (node (ref "U1") (pin "17") (pinfunction "*ACX_17") (pintype "passive"))
    )
    (net (code "95") (name "unconnected-(U1-*RDY-Pad20)") (class "Default")
      (node (ref "U1") (pin "20") (pinfunction "*RDY_20") (pintype "passive"))
    )
    (net (code "96") (name "unconnected-(U1-ACX-Pad16)") (class "Default")
      (node (ref "U1") (pin "16") (pinfunction "ACX_16") (pintype "passive"))
    )
    (net (code "97") (name "unconnected-(U1-VBIAS-Pad7)") (class "Default")
      (node (ref "U1") (pin "7") (pinfunction "VBIAS_7") (pintype "passive"))
    )
    (net (code "98") (name "unconnected-(U2-*ACX-Pad17)") (class "Default")
      (node (ref "U2") (pin "17") (pinfunction "*ACX_17") (pintype "passive"))
    )
    (net (code "99") (name "unconnected-(U2-*RDY-Pad20)") (class "Default")
      (node (ref "U2") (pin "20") (pinfunction "*RDY_20") (pintype "passive"))
    )
    (net (code "100") (name "unconnected-(U2-ACX-Pad16)") (class "Default")
      (node (ref "U2") (pin "16") (pinfunction "ACX_16") (pintype "passive"))
    )
    (net (code "101") (name "unconnected-(U2-VBIAS-Pad7)") (class "Default")
      (node (ref "U2") (pin "7") (pinfunction "VBIAS_7") (pintype "passive"))
    )
    (net (code "102") (name "unconnected-(U3-*ACX-Pad17)") (class "Default")
      (node (ref "U3") (pin "17") (pinfunction "*ACX_17") (pintype "passive"))
    )
    (net (code "103") (name "unconnected-(U3-*RDY-Pad20)") (class "Default")
      (node (ref "U3") (pin "20") (pinfunction "*RDY_20") (pintype "passive"))
    )
    (net (code "104") (name "unconnected-(U3-ACX-Pad16)") (class "Default")
      (node (ref "U3") (pin "16") (pinfunction "ACX_16") (pintype "passive"))
    )
    (net (code "105") (name "unconnected-(U3-VBIAS-Pad7)") (class "Default")
      (node (ref "U3") (pin "7") (pinfunction "VBIAS_7") (pintype "passive"))
    )
    (net (code "106") (name "unconnected-(U4-*ACX-Pad17)") (class "Default")
      (node (ref "U4") (pin "17") (pinfunction "*ACX_17") (pintype "passive"))
    )
    (net (code "107") (name "unconnected-(U4-*RDY-Pad20)") (class "Default")
      (node (ref "U4") (pin "20") (pinfunction "*RDY_20") (pintype "passive"))
    )
    (net (code "108") (name "unconnected-(U4-ACX-Pad16)") (class "Default")
      (node (ref "U4") (pin "16") (pinfunction "ACX_16") (pintype "passive"))
    )
    (net (code "109") (name "unconnected-(U4-VBIAS-Pad7)") (class "Default")
      (node (ref "U4") (pin "7") (pinfunction "VBIAS_7") (pintype "passive"))
    )
    (net (code "110") (name "unconnected-(U5-*ACX-Pad17)") (class "Default")
      (node (ref "U5") (pin "17") (pinfunction "*ACX_17") (pintype "passive"))
    )
    (net (code "111") (name "unconnected-(U5-*RDY-Pad20)") (class "Default")
      (node (ref "U5") (pin "20") (pinfunction "*RDY_20") (pintype "passive"))
    )
    (net (code "112") (name "unconnected-(U5-ACX-Pad16)") (class "Default")
      (node (ref "U5") (pin "16") (pinfunction "ACX_16") (pintype "passive"))
    )
    (net (code "113") (name "unconnected-(U5-VBIAS-Pad7)") (class "Default")
      (node (ref "U5") (pin "7") (pinfunction "VBIAS_7") (pintype "passive"))
    )
    (net (code "114") (name "unconnected-(U6-*ACX-Pad17)") (class "Default")
      (node (ref "U6") (pin "17") (pinfunction "*ACX_17") (pintype "passive"))
    )
    (net (code "115") (name "unconnected-(U6-*RDY-Pad20)") (class "Default")
      (node (ref "U6") (pin "20") (pinfunction "*RDY_20") (pintype "passive"))
    )
    (net (code "116") (name "unconnected-(U6-ACX-Pad16)") (class "Default")
      (node (ref "U6") (pin "16") (pinfunction "ACX_16") (pintype "passive"))
    )
    (net (code "117") (name "unconnected-(U6-VBIAS-Pad7)") (class "Default")
      (node (ref "U6") (pin "7") (pinfunction "VBIAS_7") (pintype "passive"))
    )
    (net (code "118") (name "unconnected-(U7-*ACX-Pad17)") (class "Default")
      (node (ref "U7") (pin "17") (pinfunction "*ACX_17") (pintype "passive"))
    )
    (net (code "119") (name "unconnected-(U7-*RDY-Pad20)") (class "Default")
      (node (ref "U7") (pin "20") (pinfunction "*RDY_20") (pintype "passive"))
    )
    (net (code "120") (name "unconnected-(U7-ACX-Pad16)") (class "Default")
      (node (ref "U7") (pin "16") (pinfunction "ACX_16") (pintype "passive"))
    )
    (net (code "121") (name "unconnected-(U7-VBIAS-Pad7)") (class "Default")
      (node (ref "U7") (pin "7") (pinfunction "VBIAS_7") (pintype "passive"))
    )
    (net (code "122") (name "unconnected-(U8-*ACX-Pad17)") (class "Default")
      (node (ref "U8") (pin "17") (pinfunction "*ACX_17") (pintype "passive"))
    )
    (net (code "123") (name "unconnected-(U8-*RDY-Pad20)") (class "Default")
      (node (ref "U8") (pin "20") (pinfunction "*RDY_20") (pintype "passive"))
    )
    (net (code "124") (name "unconnected-(U8-ACX-Pad16)") (class "Default")
      (node (ref "U8") (pin "16") (pinfunction "ACX_16") (pintype "passive"))
    )
    (net (code "125") (name "unconnected-(U8-MCLK_OUT-Pad3)") (class "Default")
      (node (ref "U8") (pin "3") (pinfunction "MCLK_OUT_3") (pintype "passive"))
    )
    (net (code "126") (name "unconnected-(U8-VBIAS-Pad7)") (class "Default")
      (node (ref "U8") (pin "7") (pinfunction "VBIAS_7") (pintype "passive"))
    )
    (net (code "127") (name "unconnected-(U9-BOOT0-Pad60)") (class "Default")
      (node (ref "U9") (pin "60") (pinfunction "BOOT0_60") (pintype "passive"))
    )
    (net (code "128") (name "unconnected-(U9-PA0-WKUP-Pad14)") (class "Default")
      (node (ref "U9") (pin "14") (pinfunction "PA0-WKUP_14") (pintype "bidirectional"))
    )
    (net (code "129") (name "unconnected-(U9-PA1-Pad15)") (class "Default")
      (node (ref "U9") (pin "15") (pinfunction "PA1_15") (pintype "bidirectional"))
    )
    (net (code "130") (name "unconnected-(U9-PA2-Pad16)") (class "Default")
      (node (ref "U9") (pin "16") (pinfunction "PA2_16") (pintype "bidirectional"))
    )
    (net (code "131") (name "unconnected-(U9-PA3-Pad17)") (class "Default")
      (node (ref "U9") (pin "17") (pinfunction "PA3_17") (pintype "bidirectional"))
    )
    (net (code "132") (name "unconnected-(U9-PA4-Pad20)") (class "Default")
      (node (ref "U9") (pin "20") (pinfunction "PA4_20") (pintype "bidirectional"))
    )
    (net (code "133") (name "unconnected-(U9-PA8-Pad41)") (class "Default")
      (node (ref "U9") (pin "41") (pinfunction "PA8_41") (pintype "bidirectional"))
    )
    (net (code "134") (name "unconnected-(U9-PA9-Pad42)") (class "Default")
      (node (ref "U9") (pin "42") (pinfunction "PA9_42") (pintype "bidirectional"))
    )
    (net (code "135") (name "unconnected-(U9-PA10-Pad43)") (class "Default")
      (node (ref "U9") (pin "43") (pinfunction "PA10_43") (pintype "bidirectional"))
    )
    (net (code "136") (name "unconnected-(U9-PA11-Pad44)") (class "Default")
      (node (ref "U9") (pin "44") (pinfunction "PA11_44") (pintype "bidirectional"))
    )
    (net (code "137") (name "unconnected-(U9-PA12-Pad45)") (class "Default")
      (node (ref "U9") (pin "45") (pinfunction "PA12_45") (pintype "bidirectional"))
    )
    (net (code "138") (name "unconnected-(U9-PB0-Pad26)") (class "Default")
      (node (ref "U9") (pin "26") (pinfunction "PB0_26") (pintype "bidirectional"))
    )
    (net (code "139") (name "unconnected-(U9-PB1-Pad27)") (class "Default")
      (node (ref "U9") (pin "27") (pinfunction "PB1_27") (pintype "bidirectional"))
    )
    (net (code "140") (name "unconnected-(U9-PB1_2-Pad28)") (class "Default")
      (node (ref "U9") (pin "28") (pinfunction "PB1_2_28") (pintype "bidirectional"))
    )
    (net (code "141") (name "unconnected-(U9-PB6-Pad58)") (class "Default")
      (node (ref "U9") (pin "58") (pinfunction "PB6_58") (pintype "bidirectional"))
    )
    (net (code "142") (name "unconnected-(U9-PB8-Pad61)") (class "Default")
      (node (ref "U9") (pin "61") (pinfunction "PB8_61") (pintype "bidirectional"))
    )
    (net (code "143") (name "unconnected-(U9-PB9-Pad62)") (class "Default")
      (node (ref "U9") (pin "62") (pinfunction "PB9_62") (pintype "bidirectional"))
    )
    (net (code "144") (name "unconnected-(U9-PB10-Pad29)") (class "Default")
      (node (ref "U9") (pin "29") (pinfunction "PB10_29") (pintype "bidirectional"))
    )
    (net (code "145") (name "unconnected-(U9-PB11-Pad30)") (class "Default")
      (node (ref "U9") (pin "30") (pinfunction "PB11_30") (pintype "bidirectional"))
    )
    (net (code "146") (name "unconnected-(U9-PB12-Pad33)") (class "Default")
      (node (ref "U9") (pin "33") (pinfunction "PB12_33") (pintype "bidirectional"))
    )
    (net (code "147") (name "unconnected-(U9-PB13-Pad34)") (class "Default")
      (node (ref "U9") (pin "34") (pinfunction "PB13_34") (pintype "bidirectional"))
    )
    (net (code "148") (name "unconnected-(U9-PB14-Pad35)") (class "Default")
      (node (ref "U9") (pin "35") (pinfunction "PB14_35") (pintype "bidirectional"))
    )
    (net (code "149") (name "unconnected-(U9-PB15-Pad36)") (class "Default")
      (node (ref "U9") (pin "36") (pinfunction "PB15_36") (pintype "bidirectional"))
    )
    (net (code "150") (name "unconnected-(U9-PC4-Pad24)") (class "Default")
      (node (ref "U9") (pin "24") (pinfunction "PC4_24") (pintype "passive"))
    )
    (net (code "151") (name "unconnected-(U9-PC5-Pad25)") (class "Default")
      (node (ref "U9") (pin "25") (pinfunction "PC5_25") (pintype "bidirectional"))
    )
    (net (code "152") (name "unconnected-(U9-PC10-Pad51)") (class "Default")
      (node (ref "U9") (pin "51") (pinfunction "PC10_51") (pintype "bidirectional"))
    )
    (net (code "153") (name "unconnected-(U9-PC11-Pad52)") (class "Default")
      (node (ref "U9") (pin "52") (pinfunction "PC11_52") (pintype "bidirectional"))
    )
    (net (code "154") (name "unconnected-(U9-PC12-Pad53)") (class "Default")
      (node (ref "U9") (pin "53") (pinfunction "PC12_53") (pintype "bidirectional"))
    )
    (net (code "155") (name "unconnected-(U9-PC13-TAMPER-RTC-Pad2)") (class "Default")
      (node (ref "U9") (pin "2") (pinfunction "PC13-TAMPER-RTC_2") (pintype "input"))
    )
    (net (code "156") (name "unconnected-(U9-PC14-OSC32_IN-Pad3)") (class "Default")
      (node (ref "U9") (pin "3") (pinfunction "PC14-OSC32_IN_3") (pintype "input"))
    )
    (net (code "157") (name "unconnected-(U9-PC15-OSC32_OUT-Pad4)") (class "Default")
      (node (ref "U9") (pin "4") (pinfunction "PC15-OSC32_OUT_4") (pintype "output"))
    )
    (net (code "158") (name "unconnected-(U9-PD2-Pad54)") (class "Default")
      (node (ref "U9") (pin "54") (pinfunction "PD2_54") (pintype "bidirectional"))
    )
    (net (code "159") (name "unconnected-(Y2-EN-Pad1)") (class "Default")
      (node (ref "Y2") (pin "1") (pinfunction "EN_1") (pintype "bidirectional"))
    )
  )
)
